# SMARTBALL_v2_0.net
KiCad netlist of a schematic drawn in EAGLE
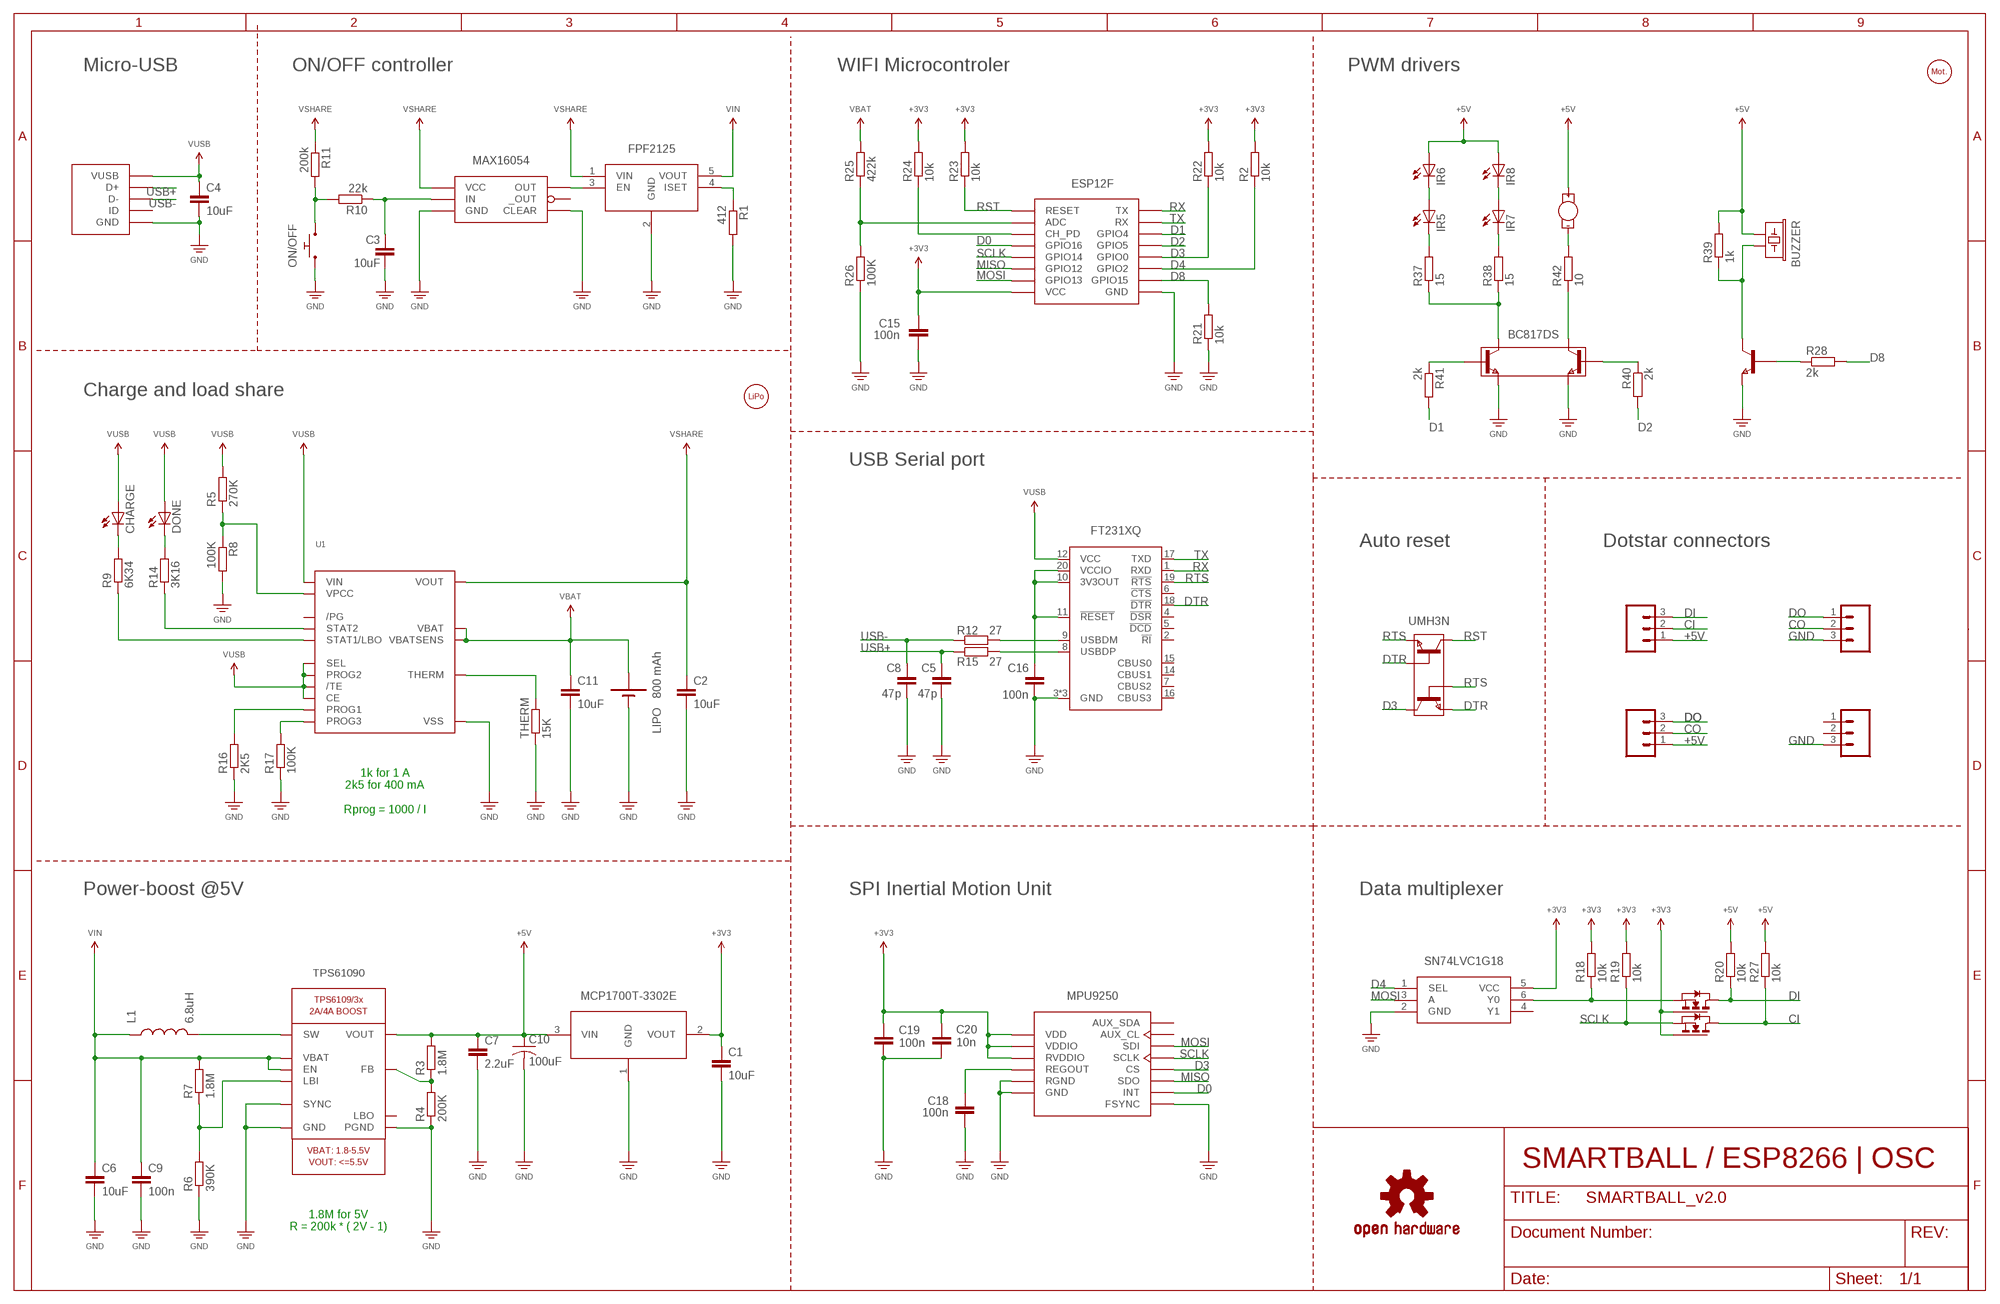
[diagram p0: schematic, sheet 1]

(export (version "E")
  (design (tool "Eeschema 10.0.6"))
  (components
    (comp (ref "BC817DS")
      (value "SOT_BC817DS")
      (footprint "eagle-import:SOT457R_PHILIPS")
      (libsource (lib "eagle-import") (part "SOT_BC817DS"))
    )
    (comp (ref "BUZZER")
      (value "BUZZER_PKMCS0909E4000-R1")
      (footprint "eagle-import:BUZZER_PKMCS0909E4000-R1")
      (libsource (lib "eagle-import") (part "BUZZER_PKMCS0909E4000-R1"))
    )
    (comp (ref "C1")
      (value "10uF")
      (footprint "eagle-import:C0603")
      (libsource (lib "eagle-import") (part "CAP_CERAMICC0603K"))
    )
    (comp (ref "C2")
      (value "10uF")
      (footprint "eagle-import:C0603")
      (libsource (lib "eagle-import") (part "CAP_CERAMICC0603K"))
    )
    (comp (ref "C3")
      (value "10uF")
      (footprint "eagle-import:C0603")
      (libsource (lib "eagle-import") (part "CAP_CERAMICC0603K"))
    )
    (comp (ref "C4")
      (value "10uF")
      (footprint "eagle-import:C0603")
      (libsource (lib "eagle-import") (part "CAP_CERAMICC0603K"))
    )
    (comp (ref "C5")
      (value "47p")
      (footprint "eagle-import:C0603")
      (libsource (lib "eagle-import") (part "CAP_CERAMICC0603K"))
    )
    (comp (ref "C6")
      (value "10uF")
      (footprint "eagle-import:C0603")
      (libsource (lib "eagle-import") (part "CAP_CERAMICC0603K"))
    )
    (comp (ref "C7")
      (value "2.2uF")
      (footprint "eagle-import:C0603")
      (libsource (lib "eagle-import") (part "CAP_CERAMICC0603K"))
    )
    (comp (ref "C8")
      (value "47p")
      (footprint "eagle-import:C0603")
      (libsource (lib "eagle-import") (part "CAP_CERAMICC0603K"))
    )
    (comp (ref "C9")
      (value "100n")
      (footprint "eagle-import:C0603")
      (libsource (lib "eagle-import") (part "CAP_CERAMICC0603K"))
    )
    (comp (ref "C10")
      (value "100uF")
      (footprint "eagle-import:C1210")
      (libsource (lib "eagle-import") (part "CAP_TANTALUMC1210"))
    )
    (comp (ref "C11")
      (value "10uF")
      (footprint "eagle-import:C0603")
      (libsource (lib "eagle-import") (part "CAP_CERAMICC0603K"))
    )
    (comp (ref "C15")
      (value "100n")
      (footprint "eagle-import:C0603")
      (libsource (lib "eagle-import") (part "CAP_CERAMICC0603K"))
    )
    (comp (ref "C16")
      (value "100n")
      (footprint "eagle-import:C0603")
      (libsource (lib "eagle-import") (part "CAP_CERAMICC0603K"))
    )
    (comp (ref "C18")
      (value "100n")
      (footprint "eagle-import:C0603")
      (libsource (lib "eagle-import") (part "CAP_CERAMICC0603K"))
    )
    (comp (ref "C19")
      (value "100n")
      (footprint "eagle-import:C0603")
      (libsource (lib "eagle-import") (part "CAP_CERAMICC0603K"))
    )
    (comp (ref "C20")
      (value "10n")
      (footprint "eagle-import:C0603")
      (libsource (lib "eagle-import") (part "CAP_CERAMICC0603K"))
    )
    (comp (ref "CHARGE")
      (value "LED_KINGBRIGHT_16X08")
      (footprint "eagle-import:LED_KINGBRIGHT_16X08")
      (libsource (lib "eagle-import") (part "LED_KINGBRIGHT_16X08"))
    )
    (comp (ref "DONE")
      (value "LED_KINGBRIGHT_16X08")
      (footprint "eagle-import:LED_KINGBRIGHT_16X08")
      (libsource (lib "eagle-import") (part "LED_KINGBRIGHT_16X08"))
    )
    (comp (ref "ESP12F")
      (value "µP_ESP12")
      (footprint "eagle-import:µP_ESP12")
      (libsource (lib "eagle-import") (part "µP_ESP12"))
    )
    (comp (ref "FT231XQ")
      (value "QFN_FT231X")
      (footprint "eagle-import:QFN20")
      (libsource (lib "eagle-import") (part "QFN_FT231X"))
    )
    (comp (ref "IR5")
      (value "LED_SFH4050")
      (footprint "eagle-import:LED_SFH4050")
      (libsource (lib "eagle-import") (part "LED_SFH4050"))
    )
    (comp (ref "IR6")
      (value "LED_SFH4050")
      (footprint "eagle-import:LED_SFH4050")
      (libsource (lib "eagle-import") (part "LED_SFH4050"))
    )
    (comp (ref "IR7")
      (value "LED_SFH4050")
      (footprint "eagle-import:LED_SFH4050")
      (libsource (lib "eagle-import") (part "LED_SFH4050"))
    )
    (comp (ref "IR8")
      (value "LED_SFH4050")
      (footprint "eagle-import:LED_SFH4050")
      (libsource (lib "eagle-import") (part "LED_SFH4050"))
    )
    (comp (ref "L1")
      (value "6.8uH")
      (footprint "eagle-import:IND_ASPIAIG-S4035")
      (libsource (lib "eagle-import") (part "IND_ASPIAIG-S4035"))
    )
    (comp (ref "LIPO")
      (value "CONN_BATTERY")
      (footprint "eagle-import:CONN_WIRES")
      (libsource (lib "eagle-import") (part "CONN_BATTERY"))
    )
    (comp (ref "LOGO1")
      (value "LOGO_OSHWL")
      (footprint "eagle-import:LOGO_OSHW")
      (libsource (lib "eagle-import") (part "LOGO_OSHWL"))
    )
    (comp (ref "MOTOR")
      (value "CONN_MOTOR")
      (footprint "eagle-import:CONN_WIRES")
      (libsource (lib "eagle-import") (part "CONN_MOTOR"))
    )
    (comp (ref "ON/OFF")
      (value "BUT_KMR6")
      (footprint "eagle-import:BUT_KMR6")
      (libsource (lib "eagle-import") (part "BUT_KMR6"))
    )
    (comp (ref "R1")
      (value "412")
      (footprint "eagle-import:R0402")
      (libsource (lib "eagle-import") (part "RES_EUR0402"))
    )
    (comp (ref "R2")
      (value "10k")
      (footprint "eagle-import:R0402")
      (libsource (lib "eagle-import") (part "RES_EUR0402"))
    )
    (comp (ref "R3")
      (value "1.8M")
      (footprint "eagle-import:R0402")
      (libsource (lib "eagle-import") (part "RES_EUR0402"))
    )
    (comp (ref "R4")
      (value "200K")
      (footprint "eagle-import:R0402")
      (libsource (lib "eagle-import") (part "RES_EUR0402"))
    )
    (comp (ref "R5")
      (value "270K")
      (footprint "eagle-import:R0402")
      (libsource (lib "eagle-import") (part "RES_EUR0402"))
    )
    (comp (ref "R6")
      (value "390K")
      (footprint "eagle-import:R0402")
      (libsource (lib "eagle-import") (part "RES_EUR0402"))
    )
    (comp (ref "R7")
      (value "1.8M")
      (footprint "eagle-import:R0402")
      (libsource (lib "eagle-import") (part "RES_EUR0402"))
    )
    (comp (ref "R8")
      (value "100K")
      (footprint "eagle-import:R0402")
      (libsource (lib "eagle-import") (part "RES_EUR0402"))
    )
    (comp (ref "R9")
      (value "6K34")
      (footprint "eagle-import:R0402")
      (libsource (lib "eagle-import") (part "RES_EUR0402"))
    )
    (comp (ref "R10")
      (value "22k")
      (footprint "eagle-import:R0402")
      (libsource (lib "eagle-import") (part "RES_EUR0402"))
    )
    (comp (ref "R11")
      (value "200k")
      (footprint "eagle-import:R0402")
      (libsource (lib "eagle-import") (part "RES_EUR0402"))
    )
    (comp (ref "R12")
      (value "27")
      (footprint "eagle-import:R0402")
      (libsource (lib "eagle-import") (part "RES_EUR0402"))
    )
    (comp (ref "R14")
      (value "3K16")
      (footprint "eagle-import:R0402")
      (libsource (lib "eagle-import") (part "RES_EUR0402"))
    )
    (comp (ref "R15")
      (value "27")
      (footprint "eagle-import:R0402")
      (libsource (lib "eagle-import") (part "RES_EUR0402"))
    )
    (comp (ref "R16")
      (value "2K5")
      (footprint "eagle-import:R0402")
      (libsource (lib "eagle-import") (part "RES_EUR0402"))
    )
    (comp (ref "R17")
      (value "100K")
      (footprint "eagle-import:R0402")
      (libsource (lib "eagle-import") (part "RES_EUR0402"))
    )
    (comp (ref "R18")
      (value "10k")
      (footprint "eagle-import:R0402")
      (libsource (lib "eagle-import") (part "RES_EUR0402"))
    )
    (comp (ref "R19")
      (value "10k")
      (footprint "eagle-import:R0402")
      (libsource (lib "eagle-import") (part "RES_EUR0402"))
    )
    (comp (ref "R20")
      (value "10k")
      (footprint "eagle-import:R0402")
      (libsource (lib "eagle-import") (part "RES_EUR0402"))
    )
    (comp (ref "R21")
      (value "10k")
      (footprint "eagle-import:R0402")
      (libsource (lib "eagle-import") (part "RES_EUR0402"))
    )
    (comp (ref "R22")
      (value "10k")
      (footprint "eagle-import:R0402")
      (libsource (lib "eagle-import") (part "RES_EUR0402"))
    )
    (comp (ref "R23")
      (value "10k")
      (footprint "eagle-import:R0402")
      (libsource (lib "eagle-import") (part "RES_EUR0402"))
    )
    (comp (ref "R24")
      (value "10k")
      (footprint "eagle-import:R0402")
      (libsource (lib "eagle-import") (part "RES_EUR0402"))
    )
    (comp (ref "R25")
      (value "422k")
      (footprint "eagle-import:R0402")
      (libsource (lib "eagle-import") (part "RES_EUR0402"))
    )
    (comp (ref "R26")
      (value "100K")
      (footprint "eagle-import:R0402")
      (libsource (lib "eagle-import") (part "RES_EUR0402"))
    )
    (comp (ref "R27")
      (value "10k")
      (footprint "eagle-import:R0402")
      (libsource (lib "eagle-import") (part "RES_EUR0402"))
    )
    (comp (ref "R28")
      (value "2k")
      (footprint "eagle-import:R0402")
      (libsource (lib "eagle-import") (part "RES_EUR0402"))
    )
    (comp (ref "R37")
      (value "15")
      (footprint "eagle-import:R0402")
      (libsource (lib "eagle-import") (part "RES_EUR0402"))
    )
    (comp (ref "R38")
      (value "15")
      (footprint "eagle-import:R0402")
      (libsource (lib "eagle-import") (part "RES_EUR0402"))
    )
    (comp (ref "R39")
      (value "1k")
      (footprint "eagle-import:R0402")
      (libsource (lib "eagle-import") (part "RES_EUR0402"))
    )
    (comp (ref "R40")
      (value "2k")
      (footprint "eagle-import:R0402")
      (libsource (lib "eagle-import") (part "RES_EUR0402"))
    )
    (comp (ref "R41")
      (value "2k")
      (footprint "eagle-import:R0402")
      (libsource (lib "eagle-import") (part "RES_EUR0402"))
    )
    (comp (ref "R42")
      (value "10")
      (footprint "eagle-import:R0402")
      (libsource (lib "eagle-import") (part "RES_EUR0402"))
    )
    (comp (ref "THERM")
      (value "15K")
      (footprint "eagle-import:R0402")
      (libsource (lib "eagle-import") (part "RES_EUR0402"))
    )
    (comp (ref "TPS61090")
      (value "TPS61090RSAR")
      (footprint "eagle-import:QFN16")
      (libsource (lib "eagle-import") (part "QFN_TPS6103X"))
    )
    (comp (ref "U$1")
      (value "CONN_USB")
      (footprint "eagle-import:CONN_USB")
      (libsource (lib "eagle-import") (part "CONN_USB"))
    )
    (comp (ref "U$2")
      (value "SOT_FPF2125")
      (footprint "eagle-import:SOT23-5")
      (libsource (lib "eagle-import") (part "SOT_FPF2125"))
    )
    (comp (ref "U$3")
      (value "SOT_MCP1700T")
      (footprint "eagle-import:SOT23-3")
      (libsource (lib "eagle-import") (part "SOT_MCP1700T"))
    )
    (comp (ref "U$5")
      (value "CONN_03_SMD")
      (footprint "eagle-import:CONN_03_SMD")
      (libsource (lib "eagle-import") (part "CONN_03_SMD"))
    )
    (comp (ref "U$6")
      (value "CONN_03_SMD")
      (footprint "eagle-import:CONN_03_SMD")
      (libsource (lib "eagle-import") (part "CONN_03_SMD"))
    )
    (comp (ref "U$12")
      (value "SOT_MAX16054")
      (footprint "eagle-import:TSOT23-6")
      (libsource (lib "eagle-import") (part "SOT_MAX16054"))
    )
    (comp (ref "U$14")
      (value "CONN_03_SMD")
      (footprint "eagle-import:CONN_03_SMD")
      (libsource (lib "eagle-import") (part "CONN_03_SMD"))
    )
    (comp (ref "U$15")
      (value "CONN_03_SMD")
      (footprint "eagle-import:CONN_03_SMD")
      (libsource (lib "eagle-import") (part "CONN_03_SMD"))
    )
    (comp (ref "U$19")
      (value "MOTOR_BODY")
      (footprint "eagle-import:MOTOR_BODY")
      (libsource (lib "eagle-import") (part "MOTOR_BODY"))
    )
    (comp (ref "U$20")
      (value "SOT_SN74LVC1G18")
      (footprint "eagle-import:SOT363")
      (libsource (lib "eagle-import") (part "SOT_SN74LVC1G18"))
    )
    (comp (ref "U$21")
      (value "QFN_MPU-9250QFN24G")
      (footprint "eagle-import:QFN24_3MM")
      (libsource (lib "eagle-import") (part "QFN_MPU-9250QFN24G"))
    )
    (comp (ref "U$22")
      (value "SOT_2N7002PS")
      (footprint "eagle-import:SOT363")
      (libsource (lib "eagle-import") (part "SOT_2N7002PS"))
    )
    (comp (ref "U$28")
      (value "SOT_SBC847AWT1G")
      (footprint "eagle-import:SOT323")
      (libsource (lib "eagle-import") (part "SOT_SBC847AWT1G"))
    )
    (comp (ref "U$29")
      (value "BATT_BODY")
      (footprint "eagle-import:BATT_BODY")
      (libsource (lib "eagle-import") (part "BATT_BODY"))
    )
    (comp (ref "U1")
      (value "QFN_MCP73871")
      (footprint "eagle-import:QFN20")
      (libsource (lib "eagle-import") (part "QFN_MCP73871"))
    )
    (comp (ref "UMH3N")
      (value "SOT_UMH3N")
      (footprint "eagle-import:SOT363")
      (libsource (lib "eagle-import") (part "SOT_UMH3N"))
    )
  )
  (nets
    (net (code "1") (name "+3V3") (class "Default")
      (node (ref "C1") (pin "1") (pinfunction "1_1") (pintype "passive"))
      (node (ref "C15") (pin "1") (pinfunction "1_1") (pintype "passive"))
      (node (ref "C19") (pin "1") (pinfunction "1_1") (pintype "passive"))
      (node (ref "C20") (pin "2") (pinfunction "2_2") (pintype "passive"))
      (node (ref "ESP12F") (pin "VCC") (pinfunction "VCC_VCC") (pintype "bidirectional"))
      (node (ref "R18") (pin "2") (pinfunction "2_2") (pintype "passive"))
      (node (ref "R19") (pin "2") (pinfunction "2_2") (pintype "passive"))
      (node (ref "R2") (pin "2") (pinfunction "2_2") (pintype "passive"))
      (node (ref "R22") (pin "2") (pinfunction "2_2") (pintype "passive"))
      (node (ref "R23") (pin "2") (pinfunction "2_2") (pintype "passive"))
      (node (ref "R24") (pin "2") (pinfunction "2_2") (pintype "passive"))
      (node (ref "U$20") (pin "5") (pinfunction "VCC_5") (pintype "bidirectional"))
      (node (ref "U$21") (pin "1") (pinfunction "RVDDIO_1") (pintype "bidirectional"))
      (node (ref "U$21") (pin "13") (pinfunction "VDD_13") (pintype "bidirectional"))
      (node (ref "U$21") (pin "8") (pinfunction "VDDIO_8") (pintype "bidirectional"))
      (node (ref "U$22") (pin "2") (pinfunction "G1_2") (pintype "passive"))
      (node (ref "U$22") (pin "5") (pinfunction "G2_5") (pintype "passive"))
      (node (ref "U$3") (pin "2") (pinfunction "VOUT_2") (pintype "bidirectional"))
    )
    (net (code "2") (name "+5V") (class "Default")
      (node (ref "BUZZER") (pin "1") (pinfunction "1_1") (pintype "passive"))
      (node (ref "C10") (pin "1") (pinfunction "1_1") (pintype "passive"))
      (node (ref "C7") (pin "1") (pinfunction "1_1") (pintype "passive"))
      (node (ref "IR6") (pin "1") (pinfunction "A_1") (pintype "passive"))
      (node (ref "IR8") (pin "1") (pinfunction "A_1") (pintype "passive"))
      (node (ref "MOTOR") (pin "VCC") (pinfunction "+_VCC") (pintype "bidirectional"))
      (node (ref "R20") (pin "2") (pinfunction "2_2") (pintype "passive"))
      (node (ref "R27") (pin "2") (pinfunction "2_2") (pintype "passive"))
      (node (ref "R3") (pin "2") (pinfunction "2_2") (pintype "passive"))
      (node (ref "R39") (pin "2") (pinfunction "2_2") (pintype "passive"))
      (node (ref "TPS61090") (pin "1") (pinfunction "VOUT_1") (pintype "power_in"))
      (node (ref "TPS61090") (pin "15") (pinfunction "VOUT_15") (pintype "power_in"))
      (node (ref "TPS61090") (pin "16") (pinfunction "VOUT_16") (pintype "power_in"))
      (node (ref "U$15") (pin "1") (pinfunction "1_1") (pintype "passive"))
      (node (ref "U$3") (pin "3") (pinfunction "VIN_3") (pintype "bidirectional"))
      (node (ref "U$5") (pin "1") (pinfunction "1_1") (pintype "passive"))
    )
    (net (code "3") (name "/CI") (class "Default")
      (node (ref "R27") (pin "1") (pinfunction "1_1") (pintype "passive"))
      (node (ref "U$22") (pin "3") (pinfunction "D2_3") (pintype "passive"))
      (node (ref "U$5") (pin "2") (pinfunction "2_2") (pintype "passive"))
    )
    (net (code "4") (name "/CO") (class "Default")
      (node (ref "U$15") (pin "2") (pinfunction "2_2") (pintype "passive"))
      (node (ref "U$6") (pin "2") (pinfunction "2_2") (pintype "passive"))
    )
    (net (code "5") (name "/D0") (class "Default")
      (node (ref "ESP12F") (pin "GPIO16") (pinfunction "GPIO16_GPIO16") (pintype "bidirectional"))
      (node (ref "U$21") (pin "12") (pinfunction "INT_12") (pintype "bidirectional"))
    )
    (net (code "6") (name "/D1") (class "Default")
      (node (ref "ESP12F") (pin "GPIO4") (pinfunction "GPIO4_GPIO4") (pintype "bidirectional"))
      (node (ref "R41") (pin "2") (pinfunction "2_2") (pintype "passive"))
    )
    (net (code "7") (name "/D2") (class "Default")
      (node (ref "ESP12F") (pin "GPIO5") (pinfunction "GPIO5_GPIO5") (pintype "bidirectional"))
      (node (ref "R40") (pin "2") (pinfunction "2_2") (pintype "passive"))
    )
    (net (code "8") (name "/D3") (class "Default")
      (node (ref "ESP12F") (pin "GPIO0") (pinfunction "GPIO0_GPIO0") (pintype "bidirectional"))
      (node (ref "R22") (pin "1") (pinfunction "1_1") (pintype "passive"))
      (node (ref "U$21") (pin "22") (pinfunction "CS_22") (pintype "bidirectional"))
      (node (ref "UMH3N") (pin "3") (pinfunction "C2_3") (pintype "passive"))
    )
    (net (code "9") (name "/D4") (class "Default")
      (node (ref "ESP12F") (pin "GPIO2") (pinfunction "GPIO2_GPIO2") (pintype "bidirectional"))
      (node (ref "R2") (pin "1") (pinfunction "1_1") (pintype "passive"))
      (node (ref "U$20") (pin "1") (pinfunction "SEL_1") (pintype "bidirectional"))
    )
    (net (code "10") (name "/D8") (class "Default")
      (node (ref "ESP12F") (pin "GPIO15") (pinfunction "GPIO15_GPIO15") (pintype "bidirectional"))
      (node (ref "R21") (pin "2") (pinfunction "2_2") (pintype "passive"))
      (node (ref "R28") (pin "2") (pinfunction "2_2") (pintype "passive"))
    )
    (net (code "11") (name "/DI") (class "Default")
      (node (ref "R20") (pin "1") (pinfunction "1_1") (pintype "passive"))
      (node (ref "U$22") (pin "6") (pinfunction "D1_6") (pintype "passive"))
      (node (ref "U$5") (pin "3") (pinfunction "3_3") (pintype "passive"))
    )
    (net (code "12") (name "/DO") (class "Default")
      (node (ref "U$15") (pin "3") (pinfunction "3_3") (pintype "passive"))
      (node (ref "U$6") (pin "1") (pinfunction "1_1") (pintype "passive"))
    )
    (net (code "13") (name "/DTR") (class "Default")
      (node (ref "FT231XQ") (pin "18") (pinfunction "~{DTR}_18") (pintype "bidirectional"))
      (node (ref "UMH3N") (pin "2") (pinfunction "B1_2") (pintype "passive"))
      (node (ref "UMH3N") (pin "4") (pinfunction "E2_4") (pintype "passive"))
    )
    (net (code "14") (name "/MISO") (class "Default")
      (node (ref "ESP12F") (pin "GPIO12") (pinfunction "GPIO12_GPIO12") (pintype "bidirectional"))
      (node (ref "U$21") (pin "9") (pinfunction "SDO_9") (pintype "bidirectional"))
    )
    (net (code "15") (name "/MOSI") (class "Default")
      (node (ref "ESP12F") (pin "GPIO13") (pinfunction "GPIO13_GPIO13") (pintype "bidirectional"))
      (node (ref "U$20") (pin "3") (pinfunction "A_3") (pintype "bidirectional"))
      (node (ref "U$21") (pin "24") (pinfunction "SDI_24") (pintype "bidirectional"))
    )
    (net (code "16") (name "/RST") (class "Default")
      (node (ref "ESP12F") (pin "RESET") (pinfunction "RESET_RESET") (pintype "bidirectional"))
      (node (ref "R23") (pin "1") (pinfunction "1_1") (pintype "passive"))
      (node (ref "UMH3N") (pin "6") (pinfunction "C1_6") (pintype "passive"))
    )
    (net (code "17") (name "/RTS") (class "Default")
      (node (ref "FT231XQ") (pin "19") (pinfunction "~{RTS}_19") (pintype "bidirectional"))
      (node (ref "UMH3N") (pin "1") (pinfunction "E1_1") (pintype "passive"))
      (node (ref "UMH3N") (pin "5") (pinfunction "B2_5") (pintype "passive"))
    )
    (net (code "18") (name "/RX") (class "Default")
      (node (ref "ESP12F") (pin "TX") (pinfunction "TX_TX") (pintype "bidirectional"))
      (node (ref "FT231XQ") (pin "1") (pinfunction "RXD_1") (pintype "bidirectional"))
    )
    (net (code "19") (name "/SCLK") (class "Default")
      (node (ref "ESP12F") (pin "GPIO14") (pinfunction "GPIO14_GPIO14") (pintype "bidirectional"))
      (node (ref "R19") (pin "1") (pinfunction "1_1") (pintype "passive"))
      (node (ref "U$21") (pin "23") (pinfunction "SCLK_23") (pintype "bidirectional"))
      (node (ref "U$22") (pin "4") (pinfunction "S2_4") (pintype "passive"))
    )
    (net (code "20") (name "/TX") (class "Default")
      (node (ref "ESP12F") (pin "RX") (pinfunction "RX_RX") (pintype "bidirectional"))
      (node (ref "FT231XQ") (pin "17") (pinfunction "TXD_17") (pintype "bidirectional"))
    )
    (net (code "21") (name "/USB+") (class "Default")
      (node (ref "C5") (pin "1") (pinfunction "1_1") (pintype "passive"))
      (node (ref "R15") (pin "1") (pinfunction "1_1") (pintype "passive"))
      (node (ref "U$1") (pin "D+") (pinfunction "D+_D+") (pintype "bidirectional"))
    )
    (net (code "22") (name "/USB-") (class "Default")
      (node (ref "C8") (pin "1") (pinfunction "1_1") (pintype "passive"))
      (node (ref "R12") (pin "1") (pinfunction "1_1") (pintype "passive"))
      (node (ref "U$1") (pin "D-") (pinfunction "D-_D-") (pintype "bidirectional"))
    )
    (net (code "23") (name "GND") (class "Default")
      (node (ref "BC817DS") (pin "1") (pinfunction "E1_1") (pintype "passive"))
      (node (ref "BC817DS") (pin "4") (pinfunction "E2_4") (pintype "passive"))
      (node (ref "C1") (pin "2") (pinfunction "2_2") (pintype "passive"))
      (node (ref "C10") (pin "2") (pinfunction "2_2") (pintype "passive"))
      (node (ref "C11") (pin "2") (pinfunction "2_2") (pintype "passive"))
      (node (ref "C15") (pin "2") (pinfunction "2_2") (pintype "passive"))
      (node (ref "C16") (pin "2") (pinfunction "2_2") (pintype "passive"))
      (node (ref "C18") (pin "2") (pinfunction "2_2") (pintype "passive"))
      (node (ref "C19") (pin "2") (pinfunction "2_2") (pintype "passive"))
      (node (ref "C2") (pin "2") (pinfunction "2_2") (pintype "passive"))
      (node (ref "C20") (pin "1") (pinfunction "1_1") (pintype "passive"))
      (node (ref "C3") (pin "2") (pinfunction "2_2") (pintype "passive"))
      (node (ref "C4") (pin "2") (pinfunction "2_2") (pintype "passive"))
      (node (ref "C5") (pin "2") (pinfunction "2_2") (pintype "passive"))
      (node (ref "C6") (pin "2") (pinfunction "2_2") (pintype "passive"))
      (node (ref "C7") (pin "2") (pinfunction "2_2") (pintype "passive"))
      (node (ref "C8") (pin "2") (pinfunction "2_2") (pintype "passive"))
      (node (ref "C9") (pin "2") (pinfunction "2_2") (pintype "passive"))
      (node (ref "ESP12F") (pin "GND") (pinfunction "GND_GND") (pintype "bidirectional"))
      (node (ref "FT231XQ") (pin "13") (pinfunction "GND_13") (pintype "bidirectional"))
      (node (ref "FT231XQ") (pin "3") (pinfunction "GND_3") (pintype "bidirectional"))
      (node (ref "FT231XQ") (pin "EXP") (pinfunction "GND_EXP") (pintype "bidirectional"))
      (node (ref "LIPO") (pin "GND") (pinfunction "GND_GND") (pintype "power_in"))
      (node (ref "ON/OFF") (pin "1") (pinfunction "1_1") (pintype "passive"))
      (node (ref "ON/OFF") (pin "4") (pinfunction "1_4") (pintype "passive"))
      (node (ref "R1") (pin "2") (pinfunction "2_2") (pintype "passive"))
      (node (ref "R16") (pin "1") (pinfunction "1_1") (pintype "passive"))
      (node (ref "R17") (pin "1") (pinfunction "1_1") (pintype "passive"))
      (node (ref "R21") (pin "1") (pinfunction "1_1") (pintype "passive"))
      (node (ref "R26") (pin "1") (pinfunction "1_1") (pintype "passive"))
      (node (ref "R4") (pin "1") (pinfunction "1_1") (pintype "passive"))
      (node (ref "R6") (pin "1") (pinfunction "1_1") (pintype "passive"))
      (node (ref "R8") (pin "2") (pinfunction "2_2") (pintype "passive"))
      (node (ref "THERM") (pin "1") (pinfunction "1_1") (pintype "passive"))
      (node (ref "TPS61090") (pin "10") (pinfunction "SYNC_10") (pintype "input"))
      (node (ref "TPS61090") (pin "13") (pinfunction "GND_13") (pintype "power_in"))
      (node (ref "TPS61090") (pin "5") (pinfunction "PGND_5") (pintype "power_in"))
      (node (ref "TPS61090") (pin "6") (pinfunction "PGND_6") (pintype "power_in"))
      (node (ref "TPS61090") (pin "7") (pinfunction "PGND_7") (pintype "power_in"))
      (node (ref "TPS61090") (pin "PAD") (pinfunction "PGND_PAD") (pintype "power_in"))
      (node (ref "U$1") (pin "GND") (pinfunction "GND_GND") (pintype "bidirectional"))
      (node (ref "U$1") (pin "P$1") (pinfunction "GND_P$1") (pintype "bidirectional"))
      (node (ref "U$1") (pin "P$11") (pinfunction "GND_P$11") (pintype "bidirectional"))
      (node (ref "U$1") (pin "SHELL1") (pinfunction "GND_SHELL1") (pintype "bidirectional"))
      (node (ref "U$1") (pin "SHELL2") (pinfunction "GND_SHELL2") (pintype "bidirectional"))
      (node (ref "U$1") (pin "SHELL5") (pinfunction "GND_SHELL5") (pintype "bidirectional"))
      (node (ref "U$1") (pin "SHELL6") (pinfunction "GND_SHELL6") (pintype "bidirectional"))
      (node (ref "U$12") (pin "2") (pinfunction "GND_2") (pintype "bidirectional"))
      (node (ref "U$12") (pin "3") (pinfunction "CLEAR_3") (pintype "bidirectional"))
      (node (ref "U$14") (pin "3") (pinfunction "3_3") (pintype "passive"))
      (node (ref "U$2") (pin "2") (pinfunction "GND_2") (pintype "bidirectional"))
      (node (ref "U$20") (pin "2") (pinfunction "GND_2") (pintype "bidirectional"))
      (node (ref "U$21") (pin "11") (pinfunction "FSYNC_11") (pintype "bidirectional"))
      (node (ref "U$21") (pin "18") (pinfunction "GND_18") (pintype "bidirectional"))
      (node (ref "U$21") (pin "20") (pinfunction "RGND_20") (pintype "bidirectional"))
      (node (ref "U$28") (pin "2") (pinfunction "E_2") (pintype "passive"))
      (node (ref "U$3") (pin "1") (pinfunction "GND_1") (pintype "bidirectional"))
      (node (ref "U$6") (pin "3") (pinfunction "3_3") (pintype "passive"))
      (node (ref "U1") (pin "10") (pinfunction "VSS_10") (pintype "bidirectional"))
      (node (ref "U1") (pin "11") (pinfunction "VSS_11") (pintype "bidirectional"))
      (node (ref "U1") (pin "EXP") (pinfunction "VSS_EXP") (pintype "bidirectional"))
    )
    (net (code "24") (name "Net-(BC817DS-B1)") (class "Default")
      (node (ref "BC817DS") (pin "2") (pinfunction "B1_2") (pintype "passive"))
      (node (ref "R40") (pin "1") (pinfunction "1_1") (pintype "passive"))
    )
    (net (code "25") (name "Net-(BC817DS-B2)") (class "Default")
      (node (ref "BC817DS") (pin "5") (pinfunction "B2_5") (pintype "passive"))
      (node (ref "R41") (pin "1") (pinfunction "1_1") (pintype "passive"))
    )
    (net (code "26") (name "Net-(BC817DS-C1)") (class "Default")
      (node (ref "BC817DS") (pin "6") (pinfunction "C1_6") (pintype "passive"))
      (node (ref "R42") (pin "1") (pinfunction "1_1") (pintype "passive"))
    )
    (net (code "27") (name "Net-(BC817DS-C2)") (class "Default")
      (node (ref "BC817DS") (pin "3") (pinfunction "C2_3") (pintype "passive"))
      (node (ref "R37") (pin "1") (pinfunction "1_1") (pintype "passive"))
      (node (ref "R38") (pin "1") (pinfunction "1_1") (pintype "passive"))
    )
    (net (code "28") (name "Net-(CHARGE-C)") (class "Default")
      (node (ref "CHARGE") (pin "2") (pinfunction "C_2") (pintype "passive"))
      (node (ref "R9") (pin "2") (pinfunction "2_2") (pintype "passive"))
    )
    (net (code "29") (name "Net-(DONE-C)") (class "Default")
      (node (ref "DONE") (pin "2") (pinfunction "C_2") (pintype "passive"))
      (node (ref "R14") (pin "2") (pinfunction "2_2") (pintype "passive"))
    )
    (net (code "30") (name "Net-(ESP12F-PadADC)") (class "Default")
      (node (ref "ESP12F") (pin "ADC") (pinfunction "ADC_ADC") (pintype "bidirectional"))
      (node (ref "R25") (pin "1") (pinfunction "1_1") (pintype "passive"))
      (node (ref "R26") (pin "2") (pinfunction "2_2") (pintype "passive"))
    )
    (net (code "31") (name "Net-(ESP12F-PadCH_PD)") (class "Default")
      (node (ref "ESP12F") (pin "CH_PD") (pinfunction "CH_PD_CH_PD") (pintype "bidirectional"))
      (node (ref "R24") (pin "1") (pinfunction "1_1") (pintype "passive"))
    )
    (net (code "32") (name "Net-(FT231XQ-3V3OUT)") (class "Default")
      (node (ref "C16") (pin "1") (pinfunction "1_1") (pintype "passive"))
      (node (ref "FT231XQ") (pin "10") (pinfunction "3V3OUT_10") (pintype "bidirectional"))
      (node (ref "FT231XQ") (pin "11") (pinfunction "~{RESET}_11") (pintype "bidirectional"))
      (node (ref "FT231XQ") (pin "20") (pinfunction "VCCIO_20") (pintype "bidirectional"))
    )
    (net (code "33") (name "Net-(FT231XQ-USBDM)") (class "Default")
      (node (ref "FT231XQ") (pin "9") (pinfunction "USBDM_9") (pintype "bidirectional"))
      (node (ref "R12") (pin "2") (pinfunction "2_2") (pintype "passive"))
    )
    (net (code "34") (name "Net-(FT231XQ-USBDP)") (class "Default")
      (node (ref "FT231XQ") (pin "8") (pinfunction "USBDP_8") (pintype "bidirectional"))
      (node (ref "R15") (pin "2") (pinfunction "2_2") (pintype "passive"))
    )
    (net (code "35") (name "Net-(IR5-A)") (class "Default")
      (node (ref "IR5") (pin "1") (pinfunction "A_1") (pintype "passive"))
      (node (ref "IR6") (pin "2") (pinfunction "C_2") (pintype "passive"))
    )
    (net (code "36") (name "Net-(IR5-C)") (class "Default")
      (node (ref "IR5") (pin "2") (pinfunction "C_2") (pintype "passive"))
      (node (ref "R37") (pin "2") (pinfunction "2_2") (pintype "passive"))
    )
    (net (code "37") (name "Net-(IR7-A)") (class "Default")
      (node (ref "IR7") (pin "1") (pinfunction "A_1") (pintype "passive"))
      (node (ref "IR8") (pin "2") (pinfunction "C_2") (pintype "passive"))
    )
    (net (code "38") (name "Net-(IR7-C)") (class "Default")
      (node (ref "IR7") (pin "2") (pinfunction "C_2") (pintype "passive"))
      (node (ref "R38") (pin "2") (pinfunction "2_2") (pintype "passive"))
    )
    (net (code "39") (name "Net-(L1-Pad2)") (class "Default")
      (node (ref "L1") (pin "2") (pinfunction "2_2") (pintype "passive"))
      (node (ref "TPS61090") (pin "3") (pinfunction "SW_3") (pintype "input"))
      (node (ref "TPS61090") (pin "4") (pinfunction "SW_4") (pintype "input"))
    )
    (net (code "40") (name "Net-(MOTOR--)") (class "Default")
      (node (ref "MOTOR") (pin "GND") (pinfunction "-_GND") (pintype "bidirectional"))
      (node (ref "R42") (pin "2") (pinfunction "2_2") (pintype "passive"))
    )
    (net (code "41") (name "Net-(ON/OFF-2-Pad3)") (class "Default")
      (node (ref "ON/OFF") (pin "2") (pinfunction "2_2") (pintype "passive"))
      (node (ref "ON/OFF") (pin "3") (pinfunction "2_3") (pintype "passive"))
      (node (ref "R10") (pin "2") (pinfunction "2_2") (pintype "passive"))
      (node (ref "R11") (pin "2") (pinfunction "2_2") (pintype "passive"))
    )
    (net (code "42") (name "Net-(TPS61090-FB)") (class "Default")
      (node (ref "R3") (pin "1") (pinfunction "1_1") (pintype "passive"))
      (node (ref "R4") (pin "2") (pinfunction "2_2") (pintype "passive"))
      (node (ref "TPS61090") (pin "14") (pinfunction "FB_14") (pintype "input"))
    )
    (net (code "43") (name "Net-(TPS61090-LBI)") (class "Default")
      (node (ref "R6") (pin "2") (pinfunction "2_2") (pintype "passive"))
      (node (ref "R7") (pin "1") (pinfunction "1_1") (pintype "passive"))
      (node (ref "TPS61090") (pin "9") (pinfunction "LBI_9") (pintype "input"))
    )
    (net (code "44") (name "Net-(U$2-ISET)") (class "Default")
      (node (ref "R1") (pin "1") (pinfunction "1_1") (pintype "passive"))
      (node (ref "U$2") (pin "4") (pinfunction "ISET_4") (pintype "bidirectional"))
    )
    (net (code "45") (name "Net-(U$12-IN)") (class "Default")
      (node (ref "C3") (pin "1") (pinfunction "1_1") (pintype "passive"))
      (node (ref "R10") (pin "1") (pinfunction "1_1") (pintype "passive"))
      (node (ref "U$12") (pin "1") (pinfunction "IN_1") (pintype "bidirectional"))
    )
    (net (code "46") (name "Net-(U$12-OUT)") (class "Default")
      (node (ref "U$12") (pin "5") (pinfunction "OUT_5") (pintype "bidirectional"))
      (node (ref "U$2") (pin "3") (pinfunction "EN_3") (pintype "bidirectional"))
    )
    (net (code "47") (name "Net-(U$20-Y0)") (class "Default")
      (node (ref "R18") (pin "1") (pinfunction "1_1") (pintype "passive"))
      (node (ref "U$20") (pin "6") (pinfunction "Y0_6") (pintype "bidirectional"))
      (node (ref "U$22") (pin "1") (pinfunction "S1_1") (pintype "passive"))
    )
    (net (code "48") (name "Net-(U$21-REGOUT)") (class "Default")
      (node (ref "C18") (pin "1") (pinfunction "1_1") (pintype "passive"))
      (node (ref "U$21") (pin "10") (pinfunction "REGOUT_10") (pintype "bidirectional"))
    )
    (net (code "49") (name "Net-(U$28-B)") (class "Default")
      (node (ref "R28") (pin "1") (pinfunction "1_1") (pintype "passive"))
      (node (ref "U$28") (pin "1") (pinfunction "B_1") (pintype "passive"))
    )
    (net (code "50") (name "Net-(U$28-C)") (class "Default")
      (node (ref "BUZZER") (pin "2") (pinfunction "2_2") (pintype "passive"))
      (node (ref "R39") (pin "1") (pinfunction "1_1") (pintype "passive"))
      (node (ref "U$28") (pin "3") (pinfunction "C_3") (pintype "passive"))
    )
    (net (code "51") (name "Net-(U1-PROG1)") (class "Default")
      (node (ref "R16") (pin "2") (pinfunction "2_2") (pintype "passive"))
      (node (ref "U1") (pin "13") (pinfunction "PROG1_13") (pintype "bidirectional"))
    )
    (net (code "52") (name "Net-(U1-PROG3)") (class "Default")
      (node (ref "R17") (pin "2") (pinfunction "2_2") (pintype "passive"))
      (node (ref "U1") (pin "12") (pinfunction "PROG3_12") (pintype "bidirectional"))
    )
    (net (code "53") (name "Net-(U1-STAT1{slash}LBO)") (class "Default")
      (node (ref "R9") (pin "1") (pinfunction "1_1") (pintype "passive"))
      (node (ref "U1") (pin "8") (pinfunction "STAT1/LBO_8") (pintype "bidirectional"))
    )
    (net (code "54") (name "Net-(U1-STAT2)") (class "Default")
      (node (ref "R14") (pin "1") (pinfunction "1_1") (pintype "passive"))
      (node (ref "U1") (pin "7") (pinfunction "STAT2_7") (pintype "bidirectional"))
    )
    (net (code "55") (name "Net-(U1-THERM)") (class "Default")
      (node (ref "THERM") (pin "2") (pinfunction "2_2") (pintype "passive"))
      (node (ref "U1") (pin "5") (pinfunction "THERM_5") (pintype "bidirectional"))
    )
    (net (code "56") (name "Net-(U1-VPCC)") (class "Default")
      (node (ref "R5") (pin "1") (pinfunction "1_1") (pintype "passive"))
      (node (ref "R8") (pin "1") (pinfunction "1_1") (pintype "passive"))
      (node (ref "U1") (pin "2") (pinfunction "VPCC_2") (pintype "bidirectional"))
    )
    (net (code "57") (name "VBAT") (class "Default")
      (node (ref "C11") (pin "1") (pinfunction "1_1") (pintype "passive"))
      (node (ref "LIPO") (pin "VCC") (pinfunction "VBAT_VCC") (pintype "power_in"))
      (node (ref "R25") (pin "2") (pinfunction "2_2") (pintype "passive"))
      (node (ref "U1") (pin "14") (pinfunction "VBAT_14") (pintype "bidirectional"))
      (node (ref "U1") (pin "15") (pinfunction "VBAT_15") (pintype "bidirectional"))
      (node (ref "U1") (pin "16") (pinfunction "VBATSENS_16") (pintype "bidirectional"))
    )
    (net (code "58") (name "VIN") (class "Default")
      (node (ref "C6") (pin "1") (pinfunction "1_1") (pintype "passive"))
      (node (ref "C9") (pin "1") (pinfunction "1_1") (pintype "passive"))
      (node (ref "L1") (pin "1") (pinfunction "1_1") (pintype "passive"))
      (node (ref "R7") (pin "2") (pinfunction "2_2") (pintype "passive"))
      (node (ref "TPS61090") (pin "11") (pinfunction "EN_11") (pintype "input"))
      (node (ref "TPS61090") (pin "8") (pinfunction "VBAT_8") (pintype "input"))
      (node (ref "U$2") (pin "5") (pinfunction "VOUT_5") (pintype "bidirectional"))
    )
    (net (code "59") (name "VSHARE") (class "Default")
      (node (ref "C2") (pin "1") (pinfunction "1_1") (pintype "passive"))
      (node (ref "R11") (pin "1") (pinfunction "1_1") (pintype "passive"))
      (node (ref "U$12") (pin "6") (pinfunction "VCC_6") (pintype "bidirectional"))
      (node (ref "U$2") (pin "1") (pinfunction "VIN_1") (pintype "bidirectional"))
      (node (ref "U1") (pin "1") (pinfunction "VOUT_1") (pintype "bidirectional"))
      (node (ref "U1") (pin "20") (pinfunction "VOUT_20") (pintype "bidirectional"))
    )
    (net (code "60") (name "VUSB") (class "Default")
      (node (ref "C4") (pin "1") (pinfunction "1_1") (pintype "passive"))
      (node (ref "CHARGE") (pin "1") (pinfunction "A_1") (pintype "passive"))
      (node (ref "DONE") (pin "1") (pinfunction "A_1") (pintype "passive"))
      (node (ref "FT231XQ") (pin "12") (pinfunction "VCC_12") (pintype "bidirectional"))
      (node (ref "R5") (pin "2") (pinfunction "2_2") (pintype "passive"))
      (node (ref "U$1") (pin "VUSB") (pinfunction "VUSB_VUSB") (pintype "bidirectional"))
      (node (ref "U1") (pin "17") (pinfunction "CE_17") (pintype "bidirectional"))
      (node (ref "U1") (pin "18") (pinfunction "VIN_18") (pintype "bidirectional"))
      (node (ref "U1") (pin "19") (pinfunction "VIN_19") (pintype "bidirectional"))
      (node (ref "U1") (pin "3") (pinfunction "SEL_3") (pintype "bidirectional"))
      (node (ref "U1") (pin "4") (pinfunction "PROG2_4") (pintype "bidirectional"))
      (node (ref "U1") (pin "9") (pinfunction "/TE_9") (pintype "bidirectional"))
    )
    (net (code "61") (name "unconnected-(FT231XQ-CBUS0-Pad15)") (class "Default")
      (node (ref "FT231XQ") (pin "15") (pinfunction "CBUS0_15") (pintype "bidirectional"))
    )
    (net (code "62") (name "unconnected-(FT231XQ-CBUS1-Pad14)") (class "Default")
      (node (ref "FT231XQ") (pin "14") (pinfunction "CBUS1_14") (pintype "bidirectional"))
    )
    (net (code "63") (name "unconnected-(FT231XQ-CBUS2-Pad7)") (class "Default")
      (node (ref "FT231XQ") (pin "7") (pinfunction "CBUS2_7") (pintype "bidirectional"))
    )
    (net (code "64") (name "unconnected-(FT231XQ-CBUS3-Pad16)") (class "Default")
      (node (ref "FT231XQ") (pin "16") (pinfunction "CBUS3_16") (pintype "bidirectional"))
    )
    (net (code "65") (name "unconnected-(FT231XQ-~{CTS}-Pad6)") (class "Default")
      (node (ref "FT231XQ") (pin "6") (pinfunction "~{CTS}_6") (pintype "bidirectional"))
    )
    (net (code "66") (name "unconnected-(FT231XQ-~{DCD}-Pad5)") (class "Default")
      (node (ref "FT231XQ") (pin "5") (pinfunction "~{DCD}_5") (pintype "bidirectional"))
    )
    (net (code "67") (name "unconnected-(FT231XQ-~{DSR}-Pad4)") (class "Default")
      (node (ref "FT231XQ") (pin "4") (pinfunction "~{DSR}_4") (pintype "bidirectional"))
    )
    (net (code "68") (name "unconnected-(FT231XQ-~{RI}-Pad2)") (class "Default")
      (node (ref "FT231XQ") (pin "2") (pinfunction "~{RI}_2") (pintype "bidirectional"))
    )
    (net (code "69") (name "unconnected-(TPS61090-LBO-Pad12)") (class "Default")
      (node (ref "TPS61090") (pin "12") (pinfunction "LBO_12") (pintype "output"))
    )
    (net (code "70") (name "unconnected-(U$1-PadID)") (class "Default")
      (node (ref "U$1") (pin "ID") (pinfunction "ID_ID") (pintype "bidirectional"))
    )
    (net (code "71") (name "unconnected-(U$12-_OUT-Pad4)") (class "Default")
      (node (ref "U$12") (pin "4") (pinfunction "_OUT_4") (pintype "bidirectional"))
    )
    (net (code "72") (name "unconnected-(U$14-Pad1)") (class "Default")
      (node (ref "U$14") (pin "1") (pinfunction "1_1") (pintype "passive"))
    )
    (net (code "73") (name "unconnected-(U$14-Pad2)") (class "Default")
      (node (ref "U$14") (pin "2") (pinfunction "2_2") (pintype "passive"))
    )
    (net (code "74") (name "unconnected-(U$20-Y1-Pad4)") (class "Default")
      (node (ref "U$20") (pin "4") (pinfunction "Y1_4") (pintype "bidirectional"))
    )
    (net (code "75") (name "unconnected-(U$21-AUX_CL-Pad7)") (class "Default")
      (node (ref "U$21") (pin "7") (pinfunction "AUX_CL_7") (pintype "bidirectional"))
    )
    (net (code "76") (name "unconnected-(U$21-AUX_SDA-Pad21)") (class "Default")
      (node (ref "U$21") (pin "21") (pinfunction "AUX_SDA_21") (pintype "bidirectional"))
    )
    (net (code "77") (name "unconnected-(U1-{slash}PG-Pad6)") (class "Default")
      (node (ref "U1") (pin "6") (pinfunction "/PG_6") (pintype "bidirectional"))
    )
  )
)
